# s1.net
KiCad netlist of a schematic drawn in EAGLE
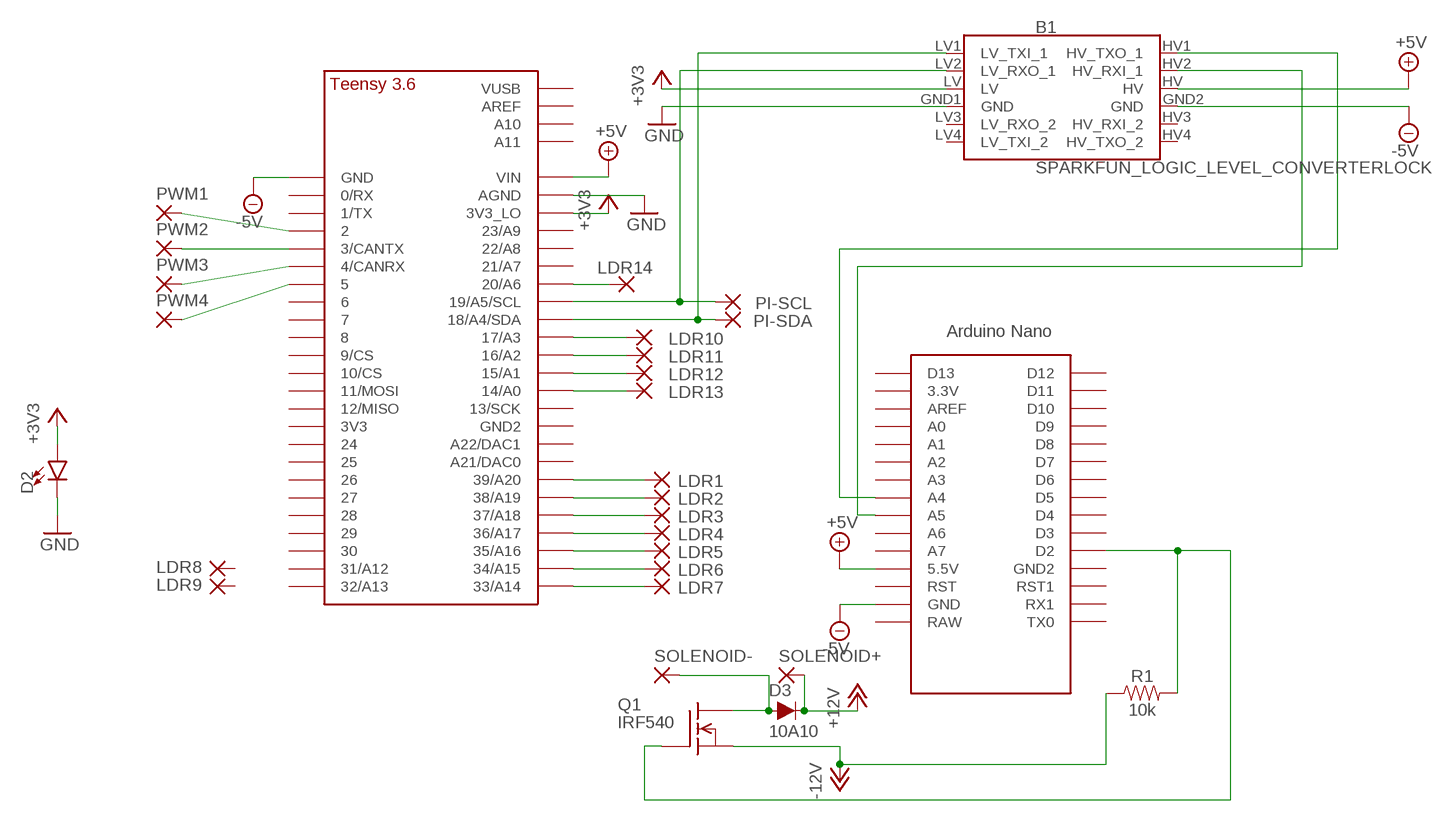
[diagram p0: schematic, sheet 1]

(export (version "E")
  (design (tool "Eeschema 10.0.6"))
  (components
    (comp (ref "B1")
      (value "SPARKFUN_LOGIC_LEVEL_CONVERTERLOCK")
      (footprint "eagle-import:SPARKFUN_LOGIC_LEVEL_CONVERTER_LOCK")
      (libsource (lib "eagle-import") (part "SPARKFUN_LOGIC_LEVEL_CONVERTERLOCK"))
    )
    (comp (ref "D2")
      (value "LED-3MM-NO_SILK")
      (footprint "eagle-import:LED_3MM-NS")
      (libsource (lib "eagle-import") (part "LED-3MM-NO_SILK"))
    )
    (comp (ref "D3")
      (value "10A10")
      (footprint "eagle-import:DIODE-1N4148")
      (libsource (lib "eagle-import") (part "DIODE-1N4148"))
    )
    (comp (ref "LDR1")
      (value "2,54/1,0")
      (footprint "eagle-import:2,54_1,0")
      (libsource (lib "eagle-import") (part "2,54/1,0"))
    )
    (comp (ref "LDR2")
      (value "2,54/1,0")
      (footprint "eagle-import:2,54_1,0")
      (libsource (lib "eagle-import") (part "2,54/1,0"))
    )
    (comp (ref "LDR3")
      (value "2,54/1,0")
      (footprint "eagle-import:2,54_1,0")
      (libsource (lib "eagle-import") (part "2,54/1,0"))
    )
    (comp (ref "LDR4")
      (value "2,54/1,0")
      (footprint "eagle-import:2,54_1,0")
      (libsource (lib "eagle-import") (part "2,54/1,0"))
    )
    (comp (ref "LDR5")
      (value "2,54/1,0")
      (footprint "eagle-import:2,54_1,0")
      (libsource (lib "eagle-import") (part "2,54/1,0"))
    )
    (comp (ref "LDR6")
      (value "2,54/1,0")
      (footprint "eagle-import:2,54_1,0")
      (libsource (lib "eagle-import") (part "2,54/1,0"))
    )
    (comp (ref "LDR7")
      (value "2,54/1,0")
      (footprint "eagle-import:2,54_1,0")
      (libsource (lib "eagle-import") (part "2,54/1,0"))
    )
    (comp (ref "LDR8")
      (value "2,54/1,0")
      (footprint "eagle-import:2,54_1,0")
      (libsource (lib "eagle-import") (part "2,54/1,0"))
    )
    (comp (ref "LDR9")
      (value "2,54/1,0")
      (footprint "eagle-import:2,54_1,0")
      (libsource (lib "eagle-import") (part "2,54/1,0"))
    )
    (comp (ref "LDR10")
      (value "2,54/1,0")
      (footprint "eagle-import:2,54_1,0")
      (libsource (lib "eagle-import") (part "2,54/1,0"))
    )
    (comp (ref "LDR11")
      (value "2,54/1,0")
      (footprint "eagle-import:2,54_1,0")
      (libsource (lib "eagle-import") (part "2,54/1,0"))
    )
    (comp (ref "LDR12")
      (value "2,54/1,0")
      (footprint "eagle-import:2,54_1,0")
      (libsource (lib "eagle-import") (part "2,54/1,0"))
    )
    (comp (ref "LDR13")
      (value "2,54/1,0")
      (footprint "eagle-import:2,54_1,0")
      (libsource (lib "eagle-import") (part "2,54/1,0"))
    )
    (comp (ref "LDR14")
      (value "2,54/1,0")
      (footprint "eagle-import:2,54_1,0")
      (libsource (lib "eagle-import") (part "2,54/1,0"))
    )
    (comp (ref "PI-SCL")
      (value "2,54/1,0")
      (footprint "eagle-import:2,54_1,0")
      (libsource (lib "eagle-import") (part "2,54/1,0"))
    )
    (comp (ref "PI-SDA")
      (value "2,54/1,0")
      (footprint "eagle-import:2,54_1,0")
      (libsource (lib "eagle-import") (part "2,54/1,0"))
    )
    (comp (ref "PWM1")
      (value "2,54/1,0")
      (footprint "eagle-import:2,54_1,0")
      (libsource (lib "eagle-import") (part "2,54/1,0"))
    )
    (comp (ref "PWM2")
      (value "2,54/1,0")
      (footprint "eagle-import:2,54_1,0")
      (libsource (lib "eagle-import") (part "2,54/1,0"))
    )
    (comp (ref "PWM3")
      (value "2,54/1,0")
      (footprint "eagle-import:2,54_1,0")
      (libsource (lib "eagle-import") (part "2,54/1,0"))
    )
    (comp (ref "PWM4")
      (value "2,54/1,0")
      (footprint "eagle-import:2,54_1,0")
      (libsource (lib "eagle-import") (part "2,54/1,0"))
    )
    (comp (ref "Q1")
      (value "IRF540")
      (footprint "eagle-import:TO220")
      (libsource (lib "eagle-import") (part "IRF540"))
    )
    (comp (ref "R1")
      (value "10k")
      (footprint "eagle-import:AXIAL-0.3")
      (libsource (lib "eagle-import") (part "10KOHM-HORIZ-1/4W-1%"))
    )
    (comp (ref "SOLENOID+")
      (value "2,54/1,0")
      (footprint "eagle-import:2,54_1,0")
      (libsource (lib "eagle-import") (part "2,54/1,0"))
    )
    (comp (ref "SOLENOID-")
      (value "2,54/1,0")
      (footprint "eagle-import:2,54_1,0")
      (libsource (lib "eagle-import") (part "2,54/1,0"))
    )
    (comp (ref "U$1")
      (value "TEENSY_3.5/3.6_BASIC")
      (footprint "eagle-import:TEENSY_3.5_3.6_BASIC")
      (libsource (lib "eagle-import") (part "TEENSY_3.5/3.6_BASIC"))
    )
    (comp (ref "U$2")
      (value "NANO")
      (footprint "eagle-import:NANO")
      (libsource (lib "eagle-import") (part "NANO"))
    )
  )
  (nets
    (net (code "1") (name "+3V3") (class "Default")
      (node (ref "B1") (pin "LV") (pinfunction "LV_LV") (pintype "power_in"))
      (node (ref "D2") (pin "A") (pinfunction "A_A") (pintype "passive"))
      (node (ref "U$1") (pin "3V3_LO") (pinfunction "3V3_LO_3V3_LO") (pintype "bidirectional"))
    )
    (net (code "2") (name "+5V") (class "Default")
      (node (ref "B1") (pin "HV") (pinfunction "HV_HV") (pintype "power_in"))
      (node (ref "U$1") (pin "VIN") (pinfunction "VIN_VIN") (pintype "bidirectional"))
      (node (ref "U$2") (pin "5V") (pinfunction "5.5V_5V") (pintype "bidirectional"))
    )
    (net (code "3") (name "+12V") (class "Default")
      (node (ref "D3") (pin "C") (pinfunction "C_C") (pintype "passive"))
      (node (ref "SOLENOID+") (pin "1") (pinfunction "P_1") (pintype "passive"))
    )
    (net (code "4") (name "-5V") (class "Default")
      (node (ref "B1") (pin "GND2") (pinfunction "GND_GND2") (pintype "power_in"))
      (node (ref "U$1") (pin "GND") (pinfunction "GND_GND") (pintype "bidirectional"))
      (node (ref "U$2") (pin "GND") (pinfunction "GND_GND") (pintype "bidirectional"))
    )
    (net (code "5") (name "-12V") (class "Default")
      (node (ref "Q1") (pin "3") (pinfunction "S_3") (pintype "passive"))
      (node (ref "R1") (pin "P$1") (pinfunction "1_P$1") (pintype "passive"))
    )
    (net (code "6") (name "GND") (class "Default")
      (node (ref "B1") (pin "GND1") (pinfunction "GND_GND1") (pintype "power_in"))
      (node (ref "D2") (pin "K") (pinfunction "C_K") (pintype "passive"))
      (node (ref "U$1") (pin "AGND") (pinfunction "AGND_AGND") (pintype "bidirectional"))
    )
    (net (code "7") (name "Net-(B1-HV_RXI_1)") (class "Default")
      (node (ref "B1") (pin "HV2") (pinfunction "HV_RXI_1_HV2") (pintype "bidirectional"))
      (node (ref "U$2") (pin "A5") (pinfunction "A5_A5") (pintype "bidirectional"))
    )
    (net (code "8") (name "Net-(B1-HV_TXO_1)") (class "Default")
      (node (ref "B1") (pin "HV1") (pinfunction "HV_TXO_1_HV1") (pintype "bidirectional"))
      (node (ref "U$2") (pin "A4") (pinfunction "A4_A4") (pintype "bidirectional"))
    )
    (net (code "9") (name "Net-(B1-LV_RXO_1)") (class "Default")
      (node (ref "B1") (pin "LV2") (pinfunction "LV_RXO_1_LV2") (pintype "bidirectional"))
      (node (ref "PI-SCL") (pin "1") (pinfunction "P_1") (pintype "passive"))
      (node (ref "U$1") (pin "19/A5/SCL") (pinfunction "19/A5/SCL_19/A5/SCL") (pintype "bidirectional"))
    )
    (net (code "10") (name "Net-(B1-LV_TXI_1)") (class "Default")
      (node (ref "B1") (pin "LV1") (pinfunction "LV_TXI_1_LV1") (pintype "bidirectional"))
      (node (ref "PI-SDA") (pin "1") (pinfunction "P_1") (pintype "passive"))
      (node (ref "U$1") (pin "18/A4/SDA") (pinfunction "18/A4/SDA_18/A4/SDA") (pintype "bidirectional"))
    )
    (net (code "11") (name "Net-(LDR1-P)") (class "Default")
      (node (ref "LDR1") (pin "1") (pinfunction "P_1") (pintype "passive"))
      (node (ref "U$1") (pin "39/A20") (pinfunction "39/A20_39/A20") (pintype "bidirectional"))
    )
    (net (code "12") (name "Net-(LDR2-P)") (class "Default")
      (node (ref "LDR2") (pin "1") (pinfunction "P_1") (pintype "passive"))
      (node (ref "U$1") (pin "38/A19") (pinfunction "38/A19_38/A19") (pintype "bidirectional"))
    )
    (net (code "13") (name "Net-(LDR3-P)") (class "Default")
      (node (ref "LDR3") (pin "1") (pinfunction "P_1") (pintype "passive"))
      (node (ref "U$1") (pin "37/A18") (pinfunction "37/A18_37/A18") (pintype "bidirectional"))
    )
    (net (code "14") (name "Net-(LDR4-P)") (class "Default")
      (node (ref "LDR4") (pin "1") (pinfunction "P_1") (pintype "passive"))
      (node (ref "U$1") (pin "36/A17") (pinfunction "36/A17_36/A17") (pintype "bidirectional"))
    )
    (net (code "15") (name "Net-(LDR5-P)") (class "Default")
      (node (ref "LDR5") (pin "1") (pinfunction "P_1") (pintype "passive"))
      (node (ref "U$1") (pin "35/A16") (pinfunction "35/A16_35/A16") (pintype "bidirectional"))
    )
    (net (code "16") (name "Net-(LDR6-P)") (class "Default")
      (node (ref "LDR6") (pin "1") (pinfunction "P_1") (pintype "passive"))
      (node (ref "U$1") (pin "34/A15") (pinfunction "34/A15_34/A15") (pintype "bidirectional"))
    )
    (net (code "17") (name "Net-(LDR7-P)") (class "Default")
      (node (ref "LDR7") (pin "1") (pinfunction "P_1") (pintype "passive"))
      (node (ref "U$1") (pin "33/A14") (pinfunction "33/A14_33/A14") (pintype "bidirectional"))
    )
    (net (code "18") (name "Net-(LDR10-P)") (class "Default")
      (node (ref "LDR10") (pin "1") (pinfunction "P_1") (pintype "passive"))
      (node (ref "U$1") (pin "17/A3") (pinfunction "17/A3_17/A3") (pintype "bidirectional"))
    )
    (net (code "19") (name "Net-(LDR11-P)") (class "Default")
      (node (ref "LDR11") (pin "1") (pinfunction "P_1") (pintype "passive"))
      (node (ref "U$1") (pin "16/A2") (pinfunction "16/A2_16/A2") (pintype "bidirectional"))
    )
    (net (code "20") (name "Net-(LDR12-P)") (class "Default")
      (node (ref "LDR12") (pin "1") (pinfunction "P_1") (pintype "passive"))
      (node (ref "U$1") (pin "15/A1") (pinfunction "15/A1_15/A1") (pintype "bidirectional"))
    )
    (net (code "21") (name "Net-(LDR13-P)") (class "Default")
      (node (ref "LDR13") (pin "1") (pinfunction "P_1") (pintype "passive"))
      (node (ref "U$1") (pin "14/A0") (pinfunction "14/A0_14/A0") (pintype "bidirectional"))
    )
    (net (code "22") (name "Net-(LDR14-P)") (class "Default")
      (node (ref "LDR14") (pin "1") (pinfunction "P_1") (pintype "passive"))
      (node (ref "U$1") (pin "20/A6") (pinfunction "20/A6_20/A6") (pintype "bidirectional"))
    )
    (net (code "23") (name "Net-(PWM1-P)") (class "Default")
      (node (ref "PWM1") (pin "1") (pinfunction "P_1") (pintype "passive"))
      (node (ref "U$1") (pin "2") (pinfunction "2_2") (pintype "bidirectional"))
    )
    (net (code "24") (name "Net-(PWM2-P)") (class "Default")
      (node (ref "PWM2") (pin "1") (pinfunction "P_1") (pintype "passive"))
      (node (ref "U$1") (pin "3/CANTX") (pinfunction "3/CANTX_3/CANTX") (pintype "bidirectional"))
    )
    (net (code "25") (name "Net-(PWM3-P)") (class "Default")
      (node (ref "PWM3") (pin "1") (pinfunction "P_1") (pintype "passive"))
      (node (ref "U$1") (pin "4/CANRX") (pinfunction "4/CANRX_4/CANRX") (pintype "bidirectional"))
    )
    (net (code "26") (name "Net-(PWM4-P)") (class "Default")
      (node (ref "PWM4") (pin "1") (pinfunction "P_1") (pintype "passive"))
      (node (ref "U$1") (pin "5") (pinfunction "5_5") (pintype "bidirectional"))
    )
    (net (code "27") (name "Net-(Q1-D)") (class "Default")
      (node (ref "D3") (pin "A") (pinfunction "A_A") (pintype "passive"))
      (node (ref "Q1") (pin "2") (pinfunction "D_2") (pintype "passive"))
      (node (ref "SOLENOID-") (pin "1") (pinfunction "P_1") (pintype "passive"))
    )
    (net (code "28") (name "Net-(Q1-G)") (class "Default")
      (node (ref "Q1") (pin "1") (pinfunction "G_1") (pintype "passive"))
      (node (ref "R1") (pin "P$2") (pinfunction "2_P$2") (pintype "passive"))
      (node (ref "U$2") (pin "D2") (pinfunction "D2_D2") (pintype "bidirectional"))
    )
    (net (code "29") (name "unconnected-(B1-HV_RXI_2-PadHV3)") (class "Default")
      (node (ref "B1") (pin "HV3") (pinfunction "HV_RXI_2_HV3") (pintype "bidirectional"))
    )
    (net (code "30") (name "unconnected-(B1-HV_TXO_2-PadHV4)") (class "Default")
      (node (ref "B1") (pin "HV4") (pinfunction "HV_TXO_2_HV4") (pintype "bidirectional"))
    )
    (net (code "31") (name "unconnected-(B1-LV_RXO_2-PadLV3)") (class "Default")
      (node (ref "B1") (pin "LV3") (pinfunction "LV_RXO_2_LV3") (pintype "bidirectional"))
    )
    (net (code "32") (name "unconnected-(B1-LV_TXI_2-PadLV4)") (class "Default")
      (node (ref "B1") (pin "LV4") (pinfunction "LV_TXI_2_LV4") (pintype "bidirectional"))
    )
    (net (code "33") (name "unconnected-(LDR8-P-Pad1)") (class "Default")
      (node (ref "LDR8") (pin "1") (pinfunction "P_1") (pintype "passive"))
    )
    (net (code "34") (name "unconnected-(LDR9-P-Pad1)") (class "Default")
      (node (ref "LDR9") (pin "1") (pinfunction "P_1") (pintype "passive"))
    )
    (net (code "35") (name "unconnected-(U$1-A21{slash}DAC0-Pad21{slash}DAC0)") (class "Default")
      (node (ref "U$1") (pin "21/DAC0") (pinfunction "A21/DAC0_21/DAC0") (pintype "bidirectional"))
    )
    (net (code "36") (name "unconnected-(U$1-Pad0{slash}RX)") (class "Default")
      (node (ref "U$1") (pin "0/RX") (pinfunction "0/RX_0/RX") (pintype "bidirectional"))
    )
    (net (code "37") (name "unconnected-(U$1-Pad1{slash}TX)") (class "Default")
      (node (ref "U$1") (pin "1/TX") (pinfunction "1/TX_1/TX") (pintype "bidirectional"))
    )
    (net (code "38") (name "unconnected-(U$1-Pad3V3)") (class "Default")
      (node (ref "U$1") (pin "3V3") (pinfunction "3V3_3V3") (pintype "bidirectional"))
    )
    (net (code "39") (name "unconnected-(U$1-Pad6)") (class "Default")
      (node (ref "U$1") (pin "6") (pinfunction "6_6") (pintype "bidirectional"))
    )
    (net (code "40") (name "unconnected-(U$1-Pad7)") (class "Default")
      (node (ref "U$1") (pin "7") (pinfunction "7_7") (pintype "bidirectional"))
    )
    (net (code "41") (name "unconnected-(U$1-Pad8)") (class "Default")
      (node (ref "U$1") (pin "8") (pinfunction "8_8") (pintype "bidirectional"))
    )
    (net (code "42") (name "unconnected-(U$1-Pad9{slash}CS)") (class "Default")
      (node (ref "U$1") (pin "9/CS") (pinfunction "9/CS_9/CS") (pintype "bidirectional"))
    )
    (net (code "43") (name "unconnected-(U$1-Pad10{slash}CS)") (class "Default")
      (node (ref "U$1") (pin "10/CS") (pinfunction "10/CS_10/CS") (pintype "bidirectional"))
    )
    (net (code "44") (name "unconnected-(U$1-Pad11{slash}MOSI)") (class "Default")
      (node (ref "U$1") (pin "11/MOSI") (pinfunction "11/MOSI_11/MOSI") (pintype "bidirectional"))
    )
    (net (code "45") (name "unconnected-(U$1-Pad12{slash}MISO)") (class "Default")
      (node (ref "U$1") (pin "12/MISO") (pinfunction "12/MISO_12/MISO") (pintype "bidirectional"))
    )
    (net (code "46") (name "unconnected-(U$1-Pad13{slash}SCK)") (class "Default")
      (node (ref "U$1") (pin "13/SCK") (pinfunction "13/SCK_13/SCK") (pintype "bidirectional"))
    )
    (net (code "47") (name "unconnected-(U$1-Pad21{slash}A7)") (class "Default")
      (node (ref "U$1") (pin "21/A7") (pinfunction "21/A7_21/A7") (pintype "bidirectional"))
    )
    (net (code "48") (name "unconnected-(U$1-Pad22{slash}A8)") (class "Default")
      (node (ref "U$1") (pin "22/A8") (pinfunction "22/A8_22/A8") (pintype "bidirectional"))
    )
    (net (code "49") (name "unconnected-(U$1-Pad23{slash}A9)") (class "Default")
      (node (ref "U$1") (pin "23/A9") (pinfunction "23/A9_23/A9") (pintype "bidirectional"))
    )
    (net (code "50") (name "unconnected-(U$1-Pad24)") (class "Default")
      (node (ref "U$1") (pin "24") (pinfunction "24_24") (pintype "bidirectional"))
    )
    (net (code "51") (name "unconnected-(U$1-Pad25)") (class "Default")
      (node (ref "U$1") (pin "25") (pinfunction "25_25") (pintype "bidirectional"))
    )
    (net (code "52") (name "unconnected-(U$1-Pad26)") (class "Default")
      (node (ref "U$1") (pin "26") (pinfunction "26_26") (pintype "bidirectional"))
    )
    (net (code "53") (name "unconnected-(U$1-Pad27)") (class "Default")
      (node (ref "U$1") (pin "27") (pinfunction "27_27") (pintype "bidirectional"))
    )
    (net (code "54") (name "unconnected-(U$1-Pad28)") (class "Default")
      (node (ref "U$1") (pin "28") (pinfunction "28_28") (pintype "bidirectional"))
    )
    (net (code "55") (name "unconnected-(U$1-Pad29)") (class "Default")
      (node (ref "U$1") (pin "29") (pinfunction "29_29") (pintype "bidirectional"))
    )
    (net (code "56") (name "unconnected-(U$1-Pad30)") (class "Default")
      (node (ref "U$1") (pin "30") (pinfunction "30_30") (pintype "bidirectional"))
    )
    (net (code "57") (name "unconnected-(U$1-Pad31{slash}A12)") (class "Default")
      (node (ref "U$1") (pin "31/A12") (pinfunction "31/A12_31/A12") (pintype "bidirectional"))
    )
    (net (code "58") (name "unconnected-(U$1-Pad32{slash}A13)") (class "Default")
      (node (ref "U$1") (pin "32/A13") (pinfunction "32/A13_32/A13") (pintype "bidirectional"))
    )
    (net (code "59") (name "unconnected-(U$1-PadA10)") (class "Default")
      (node (ref "U$1") (pin "A10") (pinfunction "A10_A10") (pintype "bidirectional"))
    )
    (net (code "60") (name "unconnected-(U$1-PadA11)") (class "Default")
      (node (ref "U$1") (pin "A11") (pinfunction "A11_A11") (pintype "bidirectional"))
    )
    (net (code "61") (name "unconnected-(U$1-PadA22{slash}DAC1)") (class "Default")
      (node (ref "U$1") (pin "A22/DAC1") (pinfunction "A22/DAC1_A22/DAC1") (pintype "bidirectional"))
    )
    (net (code "62") (name "unconnected-(U$1-PadAREF)") (class "Default")
      (node (ref "U$1") (pin "AREF") (pinfunction "AREF_AREF") (pintype "bidirectional"))
    )
    (net (code "63") (name "unconnected-(U$1-PadGND2)") (class "Default")
      (node (ref "U$1") (pin "GND2") (pinfunction "GND2_GND2") (pintype "bidirectional"))
    )
    (net (code "64") (name "unconnected-(U$1-PadVUSB)") (class "Default")
      (node (ref "U$1") (pin "VUSB") (pinfunction "VUSB_VUSB") (pintype "bidirectional"))
    )
    (net (code "65") (name "unconnected-(U$2-GND2-PadGND1)") (class "Default")
      (node (ref "U$2") (pin "GND1") (pinfunction "GND2_GND1") (pintype "bidirectional"))
    )
    (net (code "66") (name "unconnected-(U$2-Pad3.3V)") (class "Default")
      (node (ref "U$2") (pin "3.3V") (pinfunction "3.3V_3.3V") (pintype "bidirectional"))
    )
    (net (code "67") (name "unconnected-(U$2-PadA0)") (class "Default")
      (node (ref "U$2") (pin "A0") (pinfunction "A0_A0") (pintype "bidirectional"))
    )
    (net (code "68") (name "unconnected-(U$2-PadA1)") (class "Default")
      (node (ref "U$2") (pin "A1") (pinfunction "A1_A1") (pintype "bidirectional"))
    )
    (net (code "69") (name "unconnected-(U$2-PadA2)") (class "Default")
      (node (ref "U$2") (pin "A2") (pinfunction "A2_A2") (pintype "bidirectional"))
    )
    (net (code "70") (name "unconnected-(U$2-PadA3)") (class "Default")
      (node (ref "U$2") (pin "A3") (pinfunction "A3_A3") (pintype "bidirectional"))
    )
    (net (code "71") (name "unconnected-(U$2-PadA6)") (class "Default")
      (node (ref "U$2") (pin "A6") (pinfunction "A6_A6") (pintype "bidirectional"))
    )
    (net (code "72") (name "unconnected-(U$2-PadA7)") (class "Default")
      (node (ref "U$2") (pin "A7") (pinfunction "A7_A7") (pintype "bidirectional"))
    )
    (net (code "73") (name "unconnected-(U$2-PadAREF)") (class "Default")
      (node (ref "U$2") (pin "AREF") (pinfunction "AREF_AREF") (pintype "bidirectional"))
    )
    (net (code "74") (name "unconnected-(U$2-PadD3)") (class "Default")
      (node (ref "U$2") (pin "D3") (pinfunction "D3_D3") (pintype "bidirectional"))
    )
    (net (code "75") (name "unconnected-(U$2-PadD4)") (class "Default")
      (node (ref "U$2") (pin "D4") (pinfunction "D4_D4") (pintype "bidirectional"))
    )
    (net (code "76") (name "unconnected-(U$2-PadD5)") (class "Default")
      (node (ref "U$2") (pin "D5") (pinfunction "D5_D5") (pintype "bidirectional"))
    )
    (net (code "77") (name "unconnected-(U$2-PadD6)") (class "Default")
      (node (ref "U$2") (pin "D6") (pinfunction "D6_D6") (pintype "bidirectional"))
    )
    (net (code "78") (name "unconnected-(U$2-PadD7)") (class "Default")
      (node (ref "U$2") (pin "D7") (pinfunction "D7_D7") (pintype "bidirectional"))
    )
    (net (code "79") (name "unconnected-(U$2-PadD8)") (class "Default")
      (node (ref "U$2") (pin "D8") (pinfunction "D8_D8") (pintype "bidirectional"))
    )
    (net (code "80") (name "unconnected-(U$2-PadD9)") (class "Default")
      (node (ref "U$2") (pin "D9") (pinfunction "D9_D9") (pintype "bidirectional"))
    )
    (net (code "81") (name "unconnected-(U$2-PadD10)") (class "Default")
      (node (ref "U$2") (pin "D10") (pinfunction "D10_D10") (pintype "bidirectional"))
    )
    (net (code "82") (name "unconnected-(U$2-PadD11)") (class "Default")
      (node (ref "U$2") (pin "D11") (pinfunction "D11_D11") (pintype "bidirectional"))
    )
    (net (code "83") (name "unconnected-(U$2-PadD12)") (class "Default")
      (node (ref "U$2") (pin "D12") (pinfunction "D12_D12") (pintype "bidirectional"))
    )
    (net (code "84") (name "unconnected-(U$2-PadD13)") (class "Default")
      (node (ref "U$2") (pin "D13") (pinfunction "D13_D13") (pintype "bidirectional"))
    )
    (net (code "85") (name "unconnected-(U$2-PadICSP1)") (class "Default")
      (node (ref "U$2") (pin "ICSP1") (pinfunction "ICSP1_ICSP1") (pintype "bidirectional"))
    )
    (net (code "86") (name "unconnected-(U$2-PadICSP2)") (class "Default")
      (node (ref "U$2") (pin "ICSP2") (pinfunction "ICSP2_ICSP2") (pintype "bidirectional"))
    )
    (net (code "87") (name "unconnected-(U$2-PadICSP3)") (class "Default")
      (node (ref "U$2") (pin "ICSP3") (pinfunction "ICSP3_ICSP3") (pintype "bidirectional"))
    )
    (net (code "88") (name "unconnected-(U$2-PadICSP4)") (class "Default")
      (node (ref "U$2") (pin "ICSP4") (pinfunction "ICSP4_ICSP4") (pintype "bidirectional"))
    )
    (net (code "89") (name "unconnected-(U$2-PadICSP5)") (class "Default")
      (node (ref "U$2") (pin "ICSP5") (pinfunction "ICSP5_ICSP5") (pintype "bidirectional"))
    )
    (net (code "90") (name "unconnected-(U$2-PadICSP6)") (class "Default")
      (node (ref "U$2") (pin "ICSP6") (pinfunction "ICSP6_ICSP6") (pintype "bidirectional"))
    )
    (net (code "91") (name "unconnected-(U$2-PadRAW)") (class "Default")
      (node (ref "U$2") (pin "RAW") (pinfunction "RAW_RAW") (pintype "bidirectional"))
    )
    (net (code "92") (name "unconnected-(U$2-PadRST)") (class "Default")
      (node (ref "U$2") (pin "RST") (pinfunction "RST_RST") (pintype "bidirectional"))
    )
    (net (code "93") (name "unconnected-(U$2-PadRST1)") (class "Default")
      (node (ref "U$2") (pin "RST1") (pinfunction "RST1_RST1") (pintype "bidirectional"))
    )
    (net (code "94") (name "unconnected-(U$2-PadRX1)") (class "Default")
      (node (ref "U$2") (pin "RX1") (pinfunction "RX1_RX1") (pintype "bidirectional"))
    )
    (net (code "95") (name "unconnected-(U$2-PadTX0)") (class "Default")
      (node (ref "U$2") (pin "TX0") (pinfunction "TX0_TX0") (pintype "bidirectional"))
    )
  )
)
